# PWM_Buck_V1.net
KiCad netlist of a schematic drawn in EAGLE
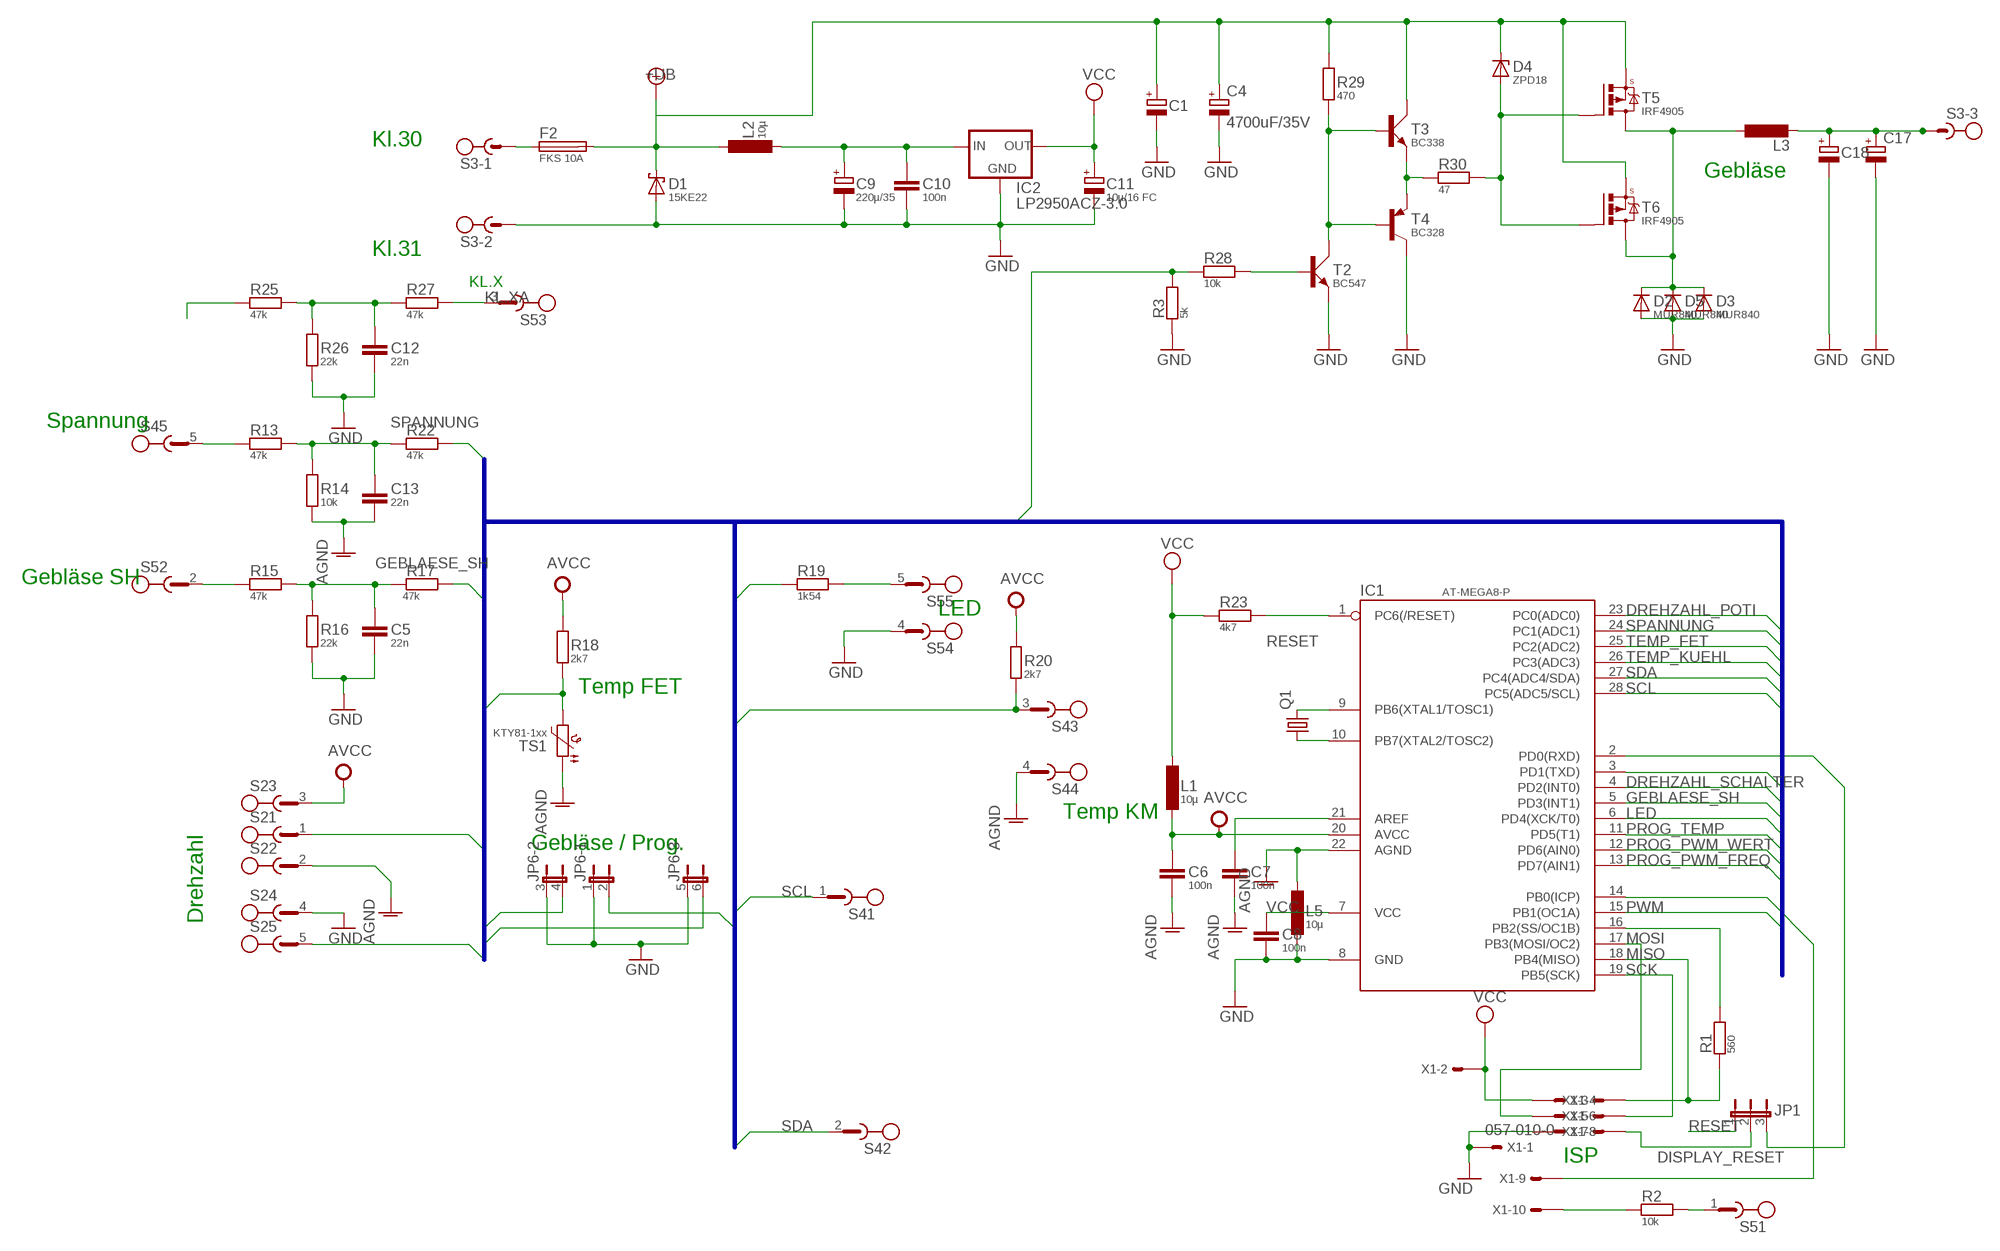
[diagram p0: schematic, sheet 1]

(export (version "E")
  (design (tool "Eeschema 10.0.6"))
  (components
    (comp (ref "C1")
      (value "C_POL_5-10.5")
      (footprint "eagle-import:E5-10.5")
      (libsource (lib "eagle-import") (part "C_POL_5-10.5"))
    )
    (comp (ref "C4")
      (value "4700uF/35V")
      (footprint "eagle-import:E7,5-18")
      (libsource (lib "eagle-import") (part "CPOL-EUE7.5-18"))
    )
    (comp (ref "C5")
      (value "22n")
      (footprint "eagle-import:C_75_SCHMAL")
      (libsource (lib "eagle-import") (part "C_75_SCHMAL"))
    )
    (comp (ref "C6")
      (value "100n")
      (footprint "eagle-import:C_50_SCHMAL")
      (libsource (lib "eagle-import") (part "C_50_SCHMAL"))
    )
    (comp (ref "C7")
      (value "100n")
      (footprint "eagle-import:C_50_SCHMAL")
      (libsource (lib "eagle-import") (part "C_50_SCHMAL"))
    )
    (comp (ref "C8")
      (value "100n")
      (footprint "eagle-import:C_50_SCHMAL")
      (libsource (lib "eagle-import") (part "C_50_SCHMAL"))
    )
    (comp (ref "C9")
      (value "220µ/35")
      (footprint "eagle-import:E5-10.5")
      (libsource (lib "eagle-import") (part "C_POL_5-10.5"))
    )
    (comp (ref "C10")
      (value "100n")
      (footprint "eagle-import:C_75_SCHMAL")
      (libsource (lib "eagle-import") (part "C_75_SCHMAL"))
    )
    (comp (ref "C11")
      (value "10µ/16 FC")
      (footprint "eagle-import:E2.5-5")
      (libsource (lib "eagle-import") (part "C_POL_2.5-5"))
    )
    (comp (ref "C12")
      (value "22n")
      (footprint "eagle-import:C_75_SCHMAL")
      (libsource (lib "eagle-import") (part "C_75_SCHMAL"))
    )
    (comp (ref "C13")
      (value "22n")
      (footprint "eagle-import:C_75_SCHMAL")
      (libsource (lib "eagle-import") (part "C_75_SCHMAL"))
    )
    (comp (ref "C17")
      (value "CPOL-EUE5-13")
      (footprint "eagle-import:E5-13")
      (libsource (lib "eagle-import") (part "CPOL-EUE5-13"))
    )
    (comp (ref "C18")
      (value "C_POL_5-10.5")
      (footprint "eagle-import:E5-10.5")
      (libsource (lib "eagle-import") (part "C_POL_5-10.5"))
    )
    (comp (ref "D1")
      (value "15KE22")
      (footprint "eagle-import:DO201T15")
      (libsource (lib "eagle-import") (part "15KEXXD"))
    )
    (comp (ref "D2")
      (value "MUR840")
      (footprint "eagle-import:TO220ACS")
      (libsource (lib "eagle-import") (part "MUR840"))
    )
    (comp (ref "D3")
      (value "MUR840")
      (footprint "eagle-import:TO220ACS")
      (libsource (lib "eagle-import") (part "MUR840"))
    )
    (comp (ref "D4")
      (value "ZPD18")
      (footprint "eagle-import:DO35Z10")
      (libsource (lib "eagle-import") (part "ZPD"))
    )
    (comp (ref "D5")
      (value "MUR840")
      (footprint "eagle-import:TO220ACS")
      (libsource (lib "eagle-import") (part "MUR840"))
    )
    (comp (ref "F2")
      (value "FKS 10A")
      (footprint "eagle-import:FKS")
      (libsource (lib "eagle-import") (part "FKS"))
    )
    (comp (ref "IC1")
      (value "AT-MEGA8-P")
      (footprint "eagle-import:AT-MEGA8P")
      (libsource (lib "eagle-import") (part "AT-MEGA8-P"))
    )
    (comp (ref "IC2")
      (value "LP2950ACZ-3.0")
      (footprint "eagle-import:TO92")
      (libsource (lib "eagle-import") (part "LP2950?ACZ-3.0"))
    )
    (comp (ref "JP1")
      (value "JP2E")
      (footprint "eagle-import:JP2")
      (libsource (lib "eagle-import") (part "JP2E"))
    )
    (comp (ref "JP6")
      (value "JP3QE")
      (footprint "eagle-import:JP3Q")
      (libsource (lib "eagle-import") (part "JP3QE"))
    )
    (comp (ref "L1")
      (value "10µ")
      (footprint "eagle-import:L-2200-12,7")
      (libsource (lib "eagle-import") (part "L-2200-12,7"))
    )
    (comp (ref "L2")
      (value "10µ")
      (footprint "eagle-import:L-2200-12,7")
      (libsource (lib "eagle-import") (part "L-2200-12,7"))
    )
    (comp (ref "L3")
      (value "L-EU0207/12")
      (footprint "eagle-import:0207_12")
      (libsource (lib "eagle-import") (part "L-EU0207/12"))
    )
    (comp (ref "L5")
      (value "10µ")
      (footprint "eagle-import:L-2200-12,7")
      (libsource (lib "eagle-import") (part "L-2200-12,7"))
    )
    (comp (ref "Q1")
      (value "CRYSTALTC26V")
      (footprint "eagle-import:TC26V")
      (libsource (lib "eagle-import") (part "CRYSTALTC26V"))
    )
    (comp (ref "R1")
      (value "560")
      (footprint "eagle-import:R_10")
      (libsource (lib "eagle-import") (part "R_10"))
    )
    (comp (ref "R2")
      (value "10k")
      (footprint "eagle-import:R_10")
      (libsource (lib "eagle-import") (part "R_10"))
    )
    (comp (ref "R3")
      (value "5k")
      (footprint "eagle-import:R_10")
      (libsource (lib "eagle-import") (part "R_10"))
    )
    (comp (ref "R13")
      (value "47k")
      (footprint "eagle-import:R_10")
      (libsource (lib "eagle-import") (part "R_10"))
    )
    (comp (ref "R14")
      (value "10k")
      (footprint "eagle-import:R_10")
      (libsource (lib "eagle-import") (part "R_10"))
    )
    (comp (ref "R15")
      (value "47k")
      (footprint "eagle-import:R_10")
      (libsource (lib "eagle-import") (part "R_10"))
    )
    (comp (ref "R16")
      (value "22k")
      (footprint "eagle-import:R_10")
      (libsource (lib "eagle-import") (part "R_10"))
    )
    (comp (ref "R17")
      (value "47k")
      (footprint "eagle-import:R_10")
      (libsource (lib "eagle-import") (part "R_10"))
    )
    (comp (ref "R18")
      (value "2k7")
      (footprint "eagle-import:R_10")
      (libsource (lib "eagle-import") (part "R_10"))
    )
    (comp (ref "R19")
      (value "1k54")
      (footprint "eagle-import:R_10")
      (libsource (lib "eagle-import") (part "R_10"))
    )
    (comp (ref "R20")
      (value "2k7")
      (footprint "eagle-import:R_12")
      (libsource (lib "eagle-import") (part "R_12"))
    )
    (comp (ref "R22")
      (value "47k")
      (footprint "eagle-import:R_10")
      (libsource (lib "eagle-import") (part "R_10"))
    )
    (comp (ref "R23")
      (value "4k7")
      (footprint "eagle-import:R_10")
      (libsource (lib "eagle-import") (part "R_10"))
    )
    (comp (ref "R25")
      (value "47k")
      (footprint "eagle-import:R_10")
      (libsource (lib "eagle-import") (part "R_10"))
    )
    (comp (ref "R26")
      (value "22k")
      (footprint "eagle-import:R_10")
      (libsource (lib "eagle-import") (part "R_10"))
    )
    (comp (ref "R27")
      (value "47k")
      (footprint "eagle-import:R_10")
      (libsource (lib "eagle-import") (part "R_10"))
    )
    (comp (ref "R28")
      (value "10k")
      (footprint "eagle-import:R_10")
      (libsource (lib "eagle-import") (part "R_10"))
    )
    (comp (ref "R29")
      (value "470")
      (footprint "eagle-import:R_10")
      (libsource (lib "eagle-import") (part "R_10"))
    )
    (comp (ref "R30")
      (value "47")
      (footprint "eagle-import:R_10")
      (libsource (lib "eagle-import") (part "R_10"))
    )
    (comp (ref "S2")
      (value "CON-PLATINE_5-POLIG")
      (footprint "eagle-import:CON-PLATINE_5-POLIG")
      (libsource (lib "eagle-import") (part "CON-PLATINE_5-POLIG"))
    )
    (comp (ref "S3")
      (value "CON-RIA-220-03")
      (footprint "eagle-import:RIA-220-03")
      (libsource (lib "eagle-import") (part "CON-RIA-220-03"))
    )
    (comp (ref "S4")
      (value "CON-RIA-183-05")
      (footprint "eagle-import:RIA-183-05")
      (libsource (lib "eagle-import") (part "CON-RIA-183-05"))
    )
    (comp (ref "S5")
      (value "CON-RIA-183-05")
      (footprint "eagle-import:RIA-183-05")
      (libsource (lib "eagle-import") (part "CON-RIA-183-05"))
    )
    (comp (ref "T2")
      (value "BC547")
      (footprint "eagle-import:SOT54A-WIDE")
      (libsource (lib "eagle-import") (part "BC547-WIDE"))
    )
    (comp (ref "T3")
      (value "BC338")
      (footprint "eagle-import:SOT54A-WIDE")
      (libsource (lib "eagle-import") (part "BC547-WIDE"))
    )
    (comp (ref "T4")
      (value "BC328")
      (footprint "eagle-import:TO92_WIDE")
      (libsource (lib "eagle-import") (part "BC557-WIDE"))
    )
    (comp (ref "T5")
      (value "IRF4905")
      (footprint "eagle-import:TO220BV")
      (libsource (lib "eagle-import") (part "MOSFET-P-IRF4905"))
    )
    (comp (ref "T6")
      (value "IRF4905")
      (footprint "eagle-import:TO220BV")
      (libsource (lib "eagle-import") (part "MOSFET-P-IRF4905"))
    )
    (comp (ref "TS1")
      (value "KTY81-1xx")
      (footprint "eagle-import:SOD70")
      (libsource (lib "eagle-import") (part "PTC-SOD70"))
    )
    (comp (ref "X1")
      (value "057-010-0")
      (footprint "eagle-import:057-010-0")
      (libsource (lib "eagle-import") (part "057-010-0"))
    )
  )
  (nets
    (net (code "1") (name "+UB") (class "Default")
      (node (ref "C1") (pin "+") (pinfunction "+_+") (pintype "passive"))
      (node (ref "C4") (pin "+") (pinfunction "+_+") (pintype "passive"))
      (node (ref "D1") (pin "C") (pinfunction "C_C") (pintype "passive"))
      (node (ref "D4") (pin "C") (pinfunction "C_C") (pintype "passive"))
      (node (ref "F2") (pin "2") (pinfunction "2_2") (pintype "passive"))
      (node (ref "L2") (pin "2") (pinfunction "2_2") (pintype "passive"))
      (node (ref "R29") (pin "2") (pinfunction "2_2") (pintype "passive"))
      (node (ref "T3") (pin "C") (pinfunction "C_C") (pintype "passive"))
      (node (ref "T5") (pin "S") (pinfunction "S_S") (pintype "passive"))
      (node (ref "T6") (pin "S") (pinfunction "S_S") (pintype "passive"))
    )
    (net (code "2") (name "/DISPLAY_RESET") (class "Default")
      (node (ref "JP1") (pin "2") (pinfunction "2_2") (pintype "passive"))
      (node (ref "X1") (pin "7") (pinfunction "S_7") (pintype "passive"))
    )
    (net (code "3") (name "/DREHZAHL_POTI") (class "Default")
      (node (ref "IC1") (pin "23") (pinfunction "PC0(ADC0)_23") (pintype "bidirectional"))
      (node (ref "S2") (pin "1") (pinfunction "SK_1") (pintype "passive"))
    )
    (net (code "4") (name "/DREHZAHL_SCHALTER") (class "Default")
      (node (ref "IC1") (pin "4") (pinfunction "PD2(INT0)_4") (pintype "bidirectional"))
      (node (ref "S2") (pin "5") (pinfunction "SK_5") (pintype "passive"))
    )
    (net (code "5") (name "/GEBLAESE_SH") (class "Default")
      (node (ref "IC1") (pin "5") (pinfunction "PD3(INT1)_5") (pintype "bidirectional"))
      (node (ref "R17") (pin "1") (pinfunction "1_1") (pintype "passive"))
    )
    (net (code "6") (name "/KL.X") (class "Default")
      (node (ref "IC1") (pin "3") (pinfunction "PD1(TXD)_3") (pintype "bidirectional"))
      (node (ref "R25") (pin "1") (pinfunction "1_1") (pintype "passive"))
    )
    (net (code "7") (name "/KL.XA") (class "Default")
      (node (ref "R27") (pin "1") (pinfunction "1_1") (pintype "passive"))
      (node (ref "S5") (pin "3") (pinfunction "SK_3") (pintype "passive"))
    )
    (net (code "8") (name "/LED") (class "Default")
      (node (ref "IC1") (pin "6") (pinfunction "PD4(XCK/T0)_6") (pintype "bidirectional"))
      (node (ref "R19") (pin "2") (pinfunction "2_2") (pintype "passive"))
    )
    (net (code "9") (name "/MISO") (class "Default")
      (node (ref "IC1") (pin "18") (pinfunction "PB4(MISO)_18") (pintype "bidirectional"))
      (node (ref "R1") (pin "1") (pinfunction "1_1") (pintype "passive"))
      (node (ref "X1") (pin "3") (pinfunction "S_3") (pintype "passive"))
    )
    (net (code "10") (name "/MOSI") (class "Default")
      (node (ref "IC1") (pin "17") (pinfunction "PB3(MOSI/OC2)_17") (pintype "bidirectional"))
      (node (ref "X1") (pin "6") (pinfunction "S_6") (pintype "passive"))
    )
    (net (code "11") (name "/PROG_PWM_FREQ") (class "Default")
      (node (ref "IC1") (pin "13") (pinfunction "PD7(AIN1)_13") (pintype "bidirectional"))
      (node (ref "JP6") (pin "6") (pinfunction "2_6") (pintype "passive"))
    )
    (net (code "12") (name "/PROG_PWM_WERT") (class "Default")
      (node (ref "IC1") (pin "12") (pinfunction "PD6(AIN0)_12") (pintype "bidirectional"))
      (node (ref "JP6") (pin "4") (pinfunction "2_4") (pintype "passive"))
    )
    (net (code "13") (name "/PROG_TEMP") (class "Default")
      (node (ref "IC1") (pin "11") (pinfunction "PD5(T1)_11") (pintype "bidirectional"))
      (node (ref "JP6") (pin "2") (pinfunction "2_2") (pintype "passive"))
    )
    (net (code "14") (name "/PWM") (class "Default")
      (node (ref "IC1") (pin "15") (pinfunction "PB1(OC1A)_15") (pintype "bidirectional"))
      (node (ref "R28") (pin "2") (pinfunction "2_2") (pintype "passive"))
      (node (ref "R3") (pin "1") (pinfunction "1_1") (pintype "passive"))
    )
    (net (code "15") (name "/RESET") (class "Default")
      (node (ref "IC1") (pin "1") (pinfunction "PC6(/RESET)_1") (pintype "bidirectional"))
      (node (ref "JP1") (pin "1") (pinfunction "1_1") (pintype "passive"))
      (node (ref "R23") (pin "2") (pinfunction "2_2") (pintype "passive"))
    )
    (net (code "16") (name "/SCK") (class "Default")
      (node (ref "IC1") (pin "19") (pinfunction "PB5(SCK)_19") (pintype "bidirectional"))
      (node (ref "X1") (pin "5") (pinfunction "S_5") (pintype "passive"))
    )
    (net (code "17") (name "/SCL") (class "Default")
      (node (ref "IC1") (pin "28") (pinfunction "PC5(ADC5/SCL)_28") (pintype "bidirectional"))
      (node (ref "S4") (pin "1") (pinfunction "SK_1") (pintype "passive"))
    )
    (net (code "18") (name "/SDA") (class "Default")
      (node (ref "IC1") (pin "27") (pinfunction "PC4(ADC4/SDA)_27") (pintype "bidirectional"))
      (node (ref "S4") (pin "2") (pinfunction "SK_2") (pintype "passive"))
    )
    (net (code "19") (name "/SPANNUNG") (class "Default")
      (node (ref "IC1") (pin "24") (pinfunction "PC1(ADC1)_24") (pintype "bidirectional"))
      (node (ref "R22") (pin "2") (pinfunction "2_2") (pintype "passive"))
    )
    (net (code "20") (name "/TEMP_FET") (class "Default")
      (node (ref "IC1") (pin "25") (pinfunction "PC2(ADC2)_25") (pintype "bidirectional"))
      (node (ref "R18") (pin "1") (pinfunction "1_1") (pintype "passive"))
      (node (ref "TS1") (pin "2") (pinfunction "2_2") (pintype "passive"))
    )
    (net (code "21") (name "/TEMP_KUEHL") (class "Default")
      (node (ref "IC1") (pin "26") (pinfunction "PC3(ADC3)_26") (pintype "bidirectional"))
      (node (ref "R20") (pin "1") (pinfunction "1_1") (pintype "passive"))
      (node (ref "S4") (pin "3") (pinfunction "SK_3") (pintype "passive"))
    )
    (net (code "22") (name "AGND") (class "Default")
      (node (ref "C13") (pin "1") (pinfunction "1_1") (pintype "passive"))
      (node (ref "C6") (pin "2") (pinfunction "2_2") (pintype "passive"))
      (node (ref "C7") (pin "2") (pinfunction "2_2") (pintype "passive"))
      (node (ref "IC1") (pin "22") (pinfunction "AGND_22") (pintype "power_in"))
      (node (ref "L5") (pin "2") (pinfunction "2_2") (pintype "passive"))
      (node (ref "R14") (pin "1") (pinfunction "1_1") (pintype "passive"))
      (node (ref "S2") (pin "2") (pinfunction "SK_2") (pintype "passive"))
      (node (ref "S4") (pin "4") (pinfunction "SK_4") (pintype "passive"))
      (node (ref "TS1") (pin "1") (pinfunction "1_1") (pintype "passive"))
    )
    (net (code "23") (name "AVCC") (class "Default")
      (node (ref "C6") (pin "1") (pinfunction "1_1") (pintype "passive"))
      (node (ref "IC1") (pin "20") (pinfunction "AVCC_20") (pintype "power_in"))
      (node (ref "L1") (pin "1") (pinfunction "1_1") (pintype "passive"))
      (node (ref "R18") (pin "2") (pinfunction "2_2") (pintype "passive"))
      (node (ref "R20") (pin "2") (pinfunction "2_2") (pintype "passive"))
      (node (ref "S2") (pin "3") (pinfunction "SK_3") (pintype "passive"))
    )
    (net (code "24") (name "GND") (class "Default")
      (node (ref "C1") (pin "-") (pinfunction "-_-") (pintype "passive"))
      (node (ref "C10") (pin "2") (pinfunction "2_2") (pintype "passive"))
      (node (ref "C11") (pin "-") (pinfunction "-_-") (pintype "passive"))
      (node (ref "C12") (pin "1") (pinfunction "1_1") (pintype "passive"))
      (node (ref "C17") (pin "-") (pinfunction "-_-") (pintype "passive"))
      (node (ref "C18") (pin "-") (pinfunction "-_-") (pintype "passive"))
      (node (ref "C4") (pin "-") (pinfunction "-_-") (pintype "passive"))
      (node (ref "C5") (pin "1") (pinfunction "1_1") (pintype "passive"))
      (node (ref "C8") (pin "2") (pinfunction "2_2") (pintype "passive"))
      (node (ref "C9") (pin "-") (pinfunction "-_-") (pintype "passive"))
      (node (ref "D1") (pin "A") (pinfunction "A_A") (pintype "passive"))
      (node (ref "D2") (pin "A") (pinfunction "A_A") (pintype "passive"))
      (node (ref "D3") (pin "A") (pinfunction "A_A") (pintype "passive"))
      (node (ref "D5") (pin "A") (pinfunction "A_A") (pintype "passive"))
      (node (ref "IC1") (pin "8") (pinfunction "GND_8") (pintype "power_in"))
      (node (ref "IC2") (pin "2") (pinfunction "GND_2") (pintype "input"))
      (node (ref "JP6") (pin "1") (pinfunction "1_1") (pintype "passive"))
      (node (ref "JP6") (pin "3") (pinfunction "1_3") (pintype "passive"))
      (node (ref "JP6") (pin "5") (pinfunction "1_5") (pintype "passive"))
      (node (ref "L5") (pin "1") (pinfunction "1_1") (pintype "passive"))
      (node (ref "R16") (pin "1") (pinfunction "1_1") (pintype "passive"))
      (node (ref "R26") (pin "1") (pinfunction "1_1") (pintype "passive"))
      (node (ref "R3") (pin "2") (pinfunction "2_2") (pintype "passive"))
      (node (ref "S2") (pin "4") (pinfunction "SK_4") (pintype "passive"))
      (node (ref "S3") (pin "2") (pinfunction "S_2") (pintype "passive"))
      (node (ref "S5") (pin "4") (pinfunction "SK_4") (pintype "passive"))
      (node (ref "T2") (pin "E") (pinfunction "E_E") (pintype "passive"))
      (node (ref "T4") (pin "3") (pinfunction "C_3") (pintype "passive"))
      (node (ref "X1") (pin "1") (pinfunction "S_1") (pintype "passive"))
      (node (ref "X1") (pin "8") (pinfunction "S_8") (pintype "passive"))
    )
    (net (code "25") (name "Net-(C5-Pad2)") (class "Default")
      (node (ref "C5") (pin "2") (pinfunction "2_2") (pintype "passive"))
      (node (ref "R15") (pin "2") (pinfunction "2_2") (pintype "passive"))
      (node (ref "R16") (pin "2") (pinfunction "2_2") (pintype "passive"))
      (node (ref "R17") (pin "2") (pinfunction "2_2") (pintype "passive"))
    )
    (net (code "26") (name "Net-(C12-Pad2)") (class "Default")
      (node (ref "C12") (pin "2") (pinfunction "2_2") (pintype "passive"))
      (node (ref "R25") (pin "2") (pinfunction "2_2") (pintype "passive"))
      (node (ref "R26") (pin "2") (pinfunction "2_2") (pintype "passive"))
      (node (ref "R27") (pin "2") (pinfunction "2_2") (pintype "passive"))
    )
    (net (code "27") (name "Net-(C13-Pad2)") (class "Default")
      (node (ref "C13") (pin "2") (pinfunction "2_2") (pintype "passive"))
      (node (ref "R13") (pin "2") (pinfunction "2_2") (pintype "passive"))
      (node (ref "R14") (pin "2") (pinfunction "2_2") (pintype "passive"))
      (node (ref "R22") (pin "1") (pinfunction "1_1") (pintype "passive"))
    )
    (net (code "28") (name "Net-(D2-PadC)") (class "Default")
      (node (ref "D2") (pin "C") (pinfunction "C_C") (pintype "passive"))
      (node (ref "D3") (pin "C") (pinfunction "C_C") (pintype "passive"))
      (node (ref "D5") (pin "C") (pinfunction "C_C") (pintype "passive"))
      (node (ref "L3") (pin "1") (pinfunction "1_1") (pintype "passive"))
      (node (ref "T5") (pin "D") (pinfunction "D_D") (pintype "passive"))
      (node (ref "T6") (pin "D") (pinfunction "D_D") (pintype "passive"))
    )
    (net (code "29") (name "Net-(D4-PadA)") (class "Default")
      (node (ref "D4") (pin "A") (pinfunction "A_A") (pintype "passive"))
      (node (ref "R30") (pin "1") (pinfunction "1_1") (pintype "passive"))
      (node (ref "T5") (pin "G") (pinfunction "G_G") (pintype "passive"))
      (node (ref "T6") (pin "G") (pinfunction "G_G") (pintype "passive"))
    )
    (net (code "30") (name "Net-(IC1-AREF)") (class "Default")
      (node (ref "C7") (pin "1") (pinfunction "1_1") (pintype "passive"))
      (node (ref "IC1") (pin "21") (pinfunction "AREF_21") (pintype "passive"))
    )
    (net (code "31") (name "Net-(IC1-PB0(ICP))") (class "Default")
      (node (ref "IC1") (pin "14") (pinfunction "PB0(ICP)_14") (pintype "bidirectional"))
      (node (ref "X1") (pin "9") (pinfunction "S_9") (pintype "passive"))
    )
    (net (code "32") (name "Net-(IC1-PB2(SS{slash}OC1B))") (class "Default")
      (node (ref "IC1") (pin "16") (pinfunction "PB2(SS/OC1B)_16") (pintype "bidirectional"))
      (node (ref "R1") (pin "2") (pinfunction "2_2") (pintype "passive"))
    )
    (net (code "33") (name "Net-(IC1-PB6(XTAL1{slash}TOSC1))") (class "Default")
      (node (ref "IC1") (pin "9") (pinfunction "PB6(XTAL1/TOSC1)_9") (pintype "bidirectional"))
      (node (ref "Q1") (pin "2") (pinfunction "2_2") (pintype "passive"))
    )
    (net (code "34") (name "Net-(IC1-PB7(XTAL2{slash}TOSC2))") (class "Default")
      (node (ref "IC1") (pin "10") (pinfunction "PB7(XTAL2/TOSC2)_10") (pintype "bidirectional"))
      (node (ref "Q1") (pin "1") (pinfunction "1_1") (pintype "passive"))
    )
    (net (code "35") (name "Net-(IC1-PD0(RXD))") (class "Default")
      (node (ref "IC1") (pin "2") (pinfunction "PD0(RXD)_2") (pintype "bidirectional"))
      (node (ref "JP1") (pin "3") (pinfunction "3_3") (pintype "passive"))
    )
    (net (code "36") (name "Net-(IC2-IN)") (class "Default")
      (node (ref "C10") (pin "1") (pinfunction "1_1") (pintype "passive"))
      (node (ref "C9") (pin "+") (pinfunction "+_+") (pintype "passive"))
      (node (ref "IC2") (pin "3") (pinfunction "IN_3") (pintype "input"))
      (node (ref "L2") (pin "1") (pinfunction "1_1") (pintype "passive"))
    )
    (net (code "37") (name "Net-(R28-Pad1)") (class "Default")
      (node (ref "R28") (pin "1") (pinfunction "1_1") (pintype "passive"))
      (node (ref "T2") (pin "B") (pinfunction "B_B") (pintype "passive"))
    )
    (net (code "38") (name "Net-(S3A-S)") (class "Default")
      (node (ref "F2") (pin "1") (pinfunction "1_1") (pintype "passive"))
      (node (ref "S3") (pin "1") (pinfunction "S_1") (pintype "passive"))
    )
    (net (code "39") (name "Net-(S3C-S)") (class "Default")
      (node (ref "C17") (pin "+") (pinfunction "+_+") (pintype "passive"))
      (node (ref "C18") (pin "+") (pinfunction "+_+") (pintype "passive"))
      (node (ref "L3") (pin "2") (pinfunction "2_2") (pintype "passive"))
      (node (ref "S3") (pin "3") (pinfunction "S_3") (pintype "passive"))
    )
    (net (code "40") (name "Net-(S4E-SK)") (class "Default")
      (node (ref "R13") (pin "1") (pinfunction "1_1") (pintype "passive"))
      (node (ref "S4") (pin "5") (pinfunction "SK_5") (pintype "passive"))
    )
    (net (code "41") (name "Net-(S5A-SK)") (class "Default")
      (node (ref "R2") (pin "1") (pinfunction "1_1") (pintype "passive"))
      (node (ref "S5") (pin "1") (pinfunction "SK_1") (pintype "passive"))
    )
    (net (code "42") (name "Net-(S5B-SK)") (class "Default")
      (node (ref "R15") (pin "1") (pinfunction "1_1") (pintype "passive"))
      (node (ref "S5") (pin "2") (pinfunction "SK_2") (pintype "passive"))
    )
    (net (code "43") (name "Net-(S5E-SK)") (class "Default")
      (node (ref "R19") (pin "1") (pinfunction "1_1") (pintype "passive"))
      (node (ref "S5") (pin "5") (pinfunction "SK_5") (pintype "passive"))
    )
    (net (code "44") (name "Net-(T4-B)") (class "Default")
      (node (ref "R29") (pin "1") (pinfunction "1_1") (pintype "passive"))
      (node (ref "T2") (pin "C") (pinfunction "C_C") (pintype "passive"))
      (node (ref "T3") (pin "B") (pinfunction "B_B") (pintype "passive"))
      (node (ref "T4") (pin "2") (pinfunction "B_2") (pintype "passive"))
    )
    (net (code "45") (name "Net-(T4-E)") (class "Default")
      (node (ref "R30") (pin "2") (pinfunction "2_2") (pintype "passive"))
      (node (ref "T3") (pin "E") (pinfunction "E_E") (pintype "passive"))
      (node (ref "T4") (pin "1") (pinfunction "E_1") (pintype "passive"))
    )
    (net (code "46") (name "Net-(X1B-S)") (class "Default")
      (node (ref "R2") (pin "2") (pinfunction "2_2") (pintype "passive"))
      (node (ref "X1") (pin "10") (pinfunction "S_10") (pintype "passive"))
    )
    (net (code "47") (name "VCC") (class "Default")
      (node (ref "C11") (pin "+") (pinfunction "+_+") (pintype "passive"))
      (node (ref "C8") (pin "1") (pinfunction "1_1") (pintype "passive"))
      (node (ref "IC1") (pin "7") (pinfunction "VCC_7") (pintype "power_in"))
      (node (ref "IC2") (pin "1") (pinfunction "OUT_1") (pintype "passive"))
      (node (ref "L1") (pin "2") (pinfunction "2_2") (pintype "passive"))
      (node (ref "R23") (pin "1") (pinfunction "1_1") (pintype "passive"))
      (node (ref "X1") (pin "2") (pinfunction "S_2") (pintype "passive"))
      (node (ref "X1") (pin "4") (pinfunction "S_4") (pintype "passive"))
    )
  )
)
